# Feather-RTD.net
KiCad netlist of a schematic drawn in EAGLE
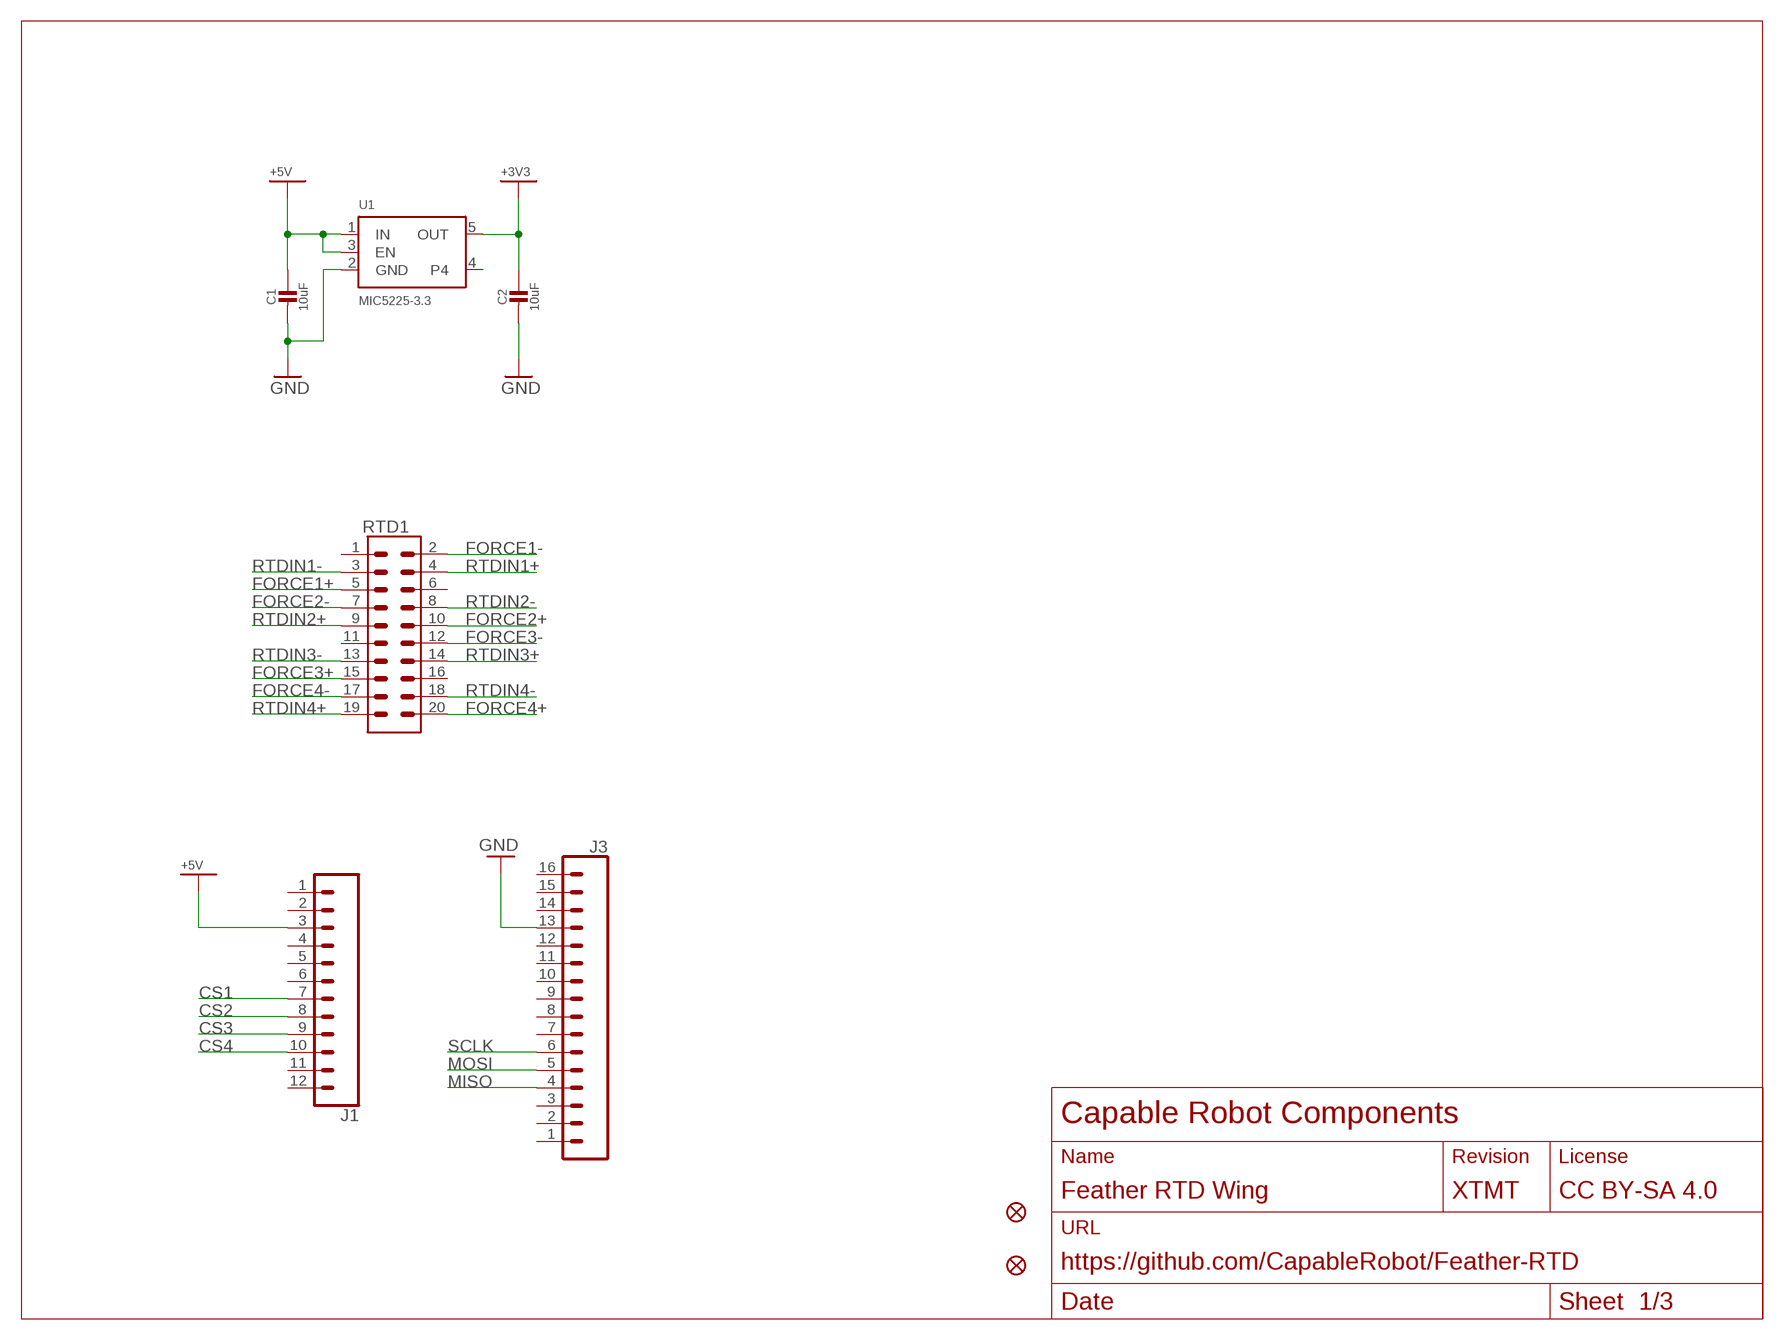
[diagram p0: schematic, sheet 1]
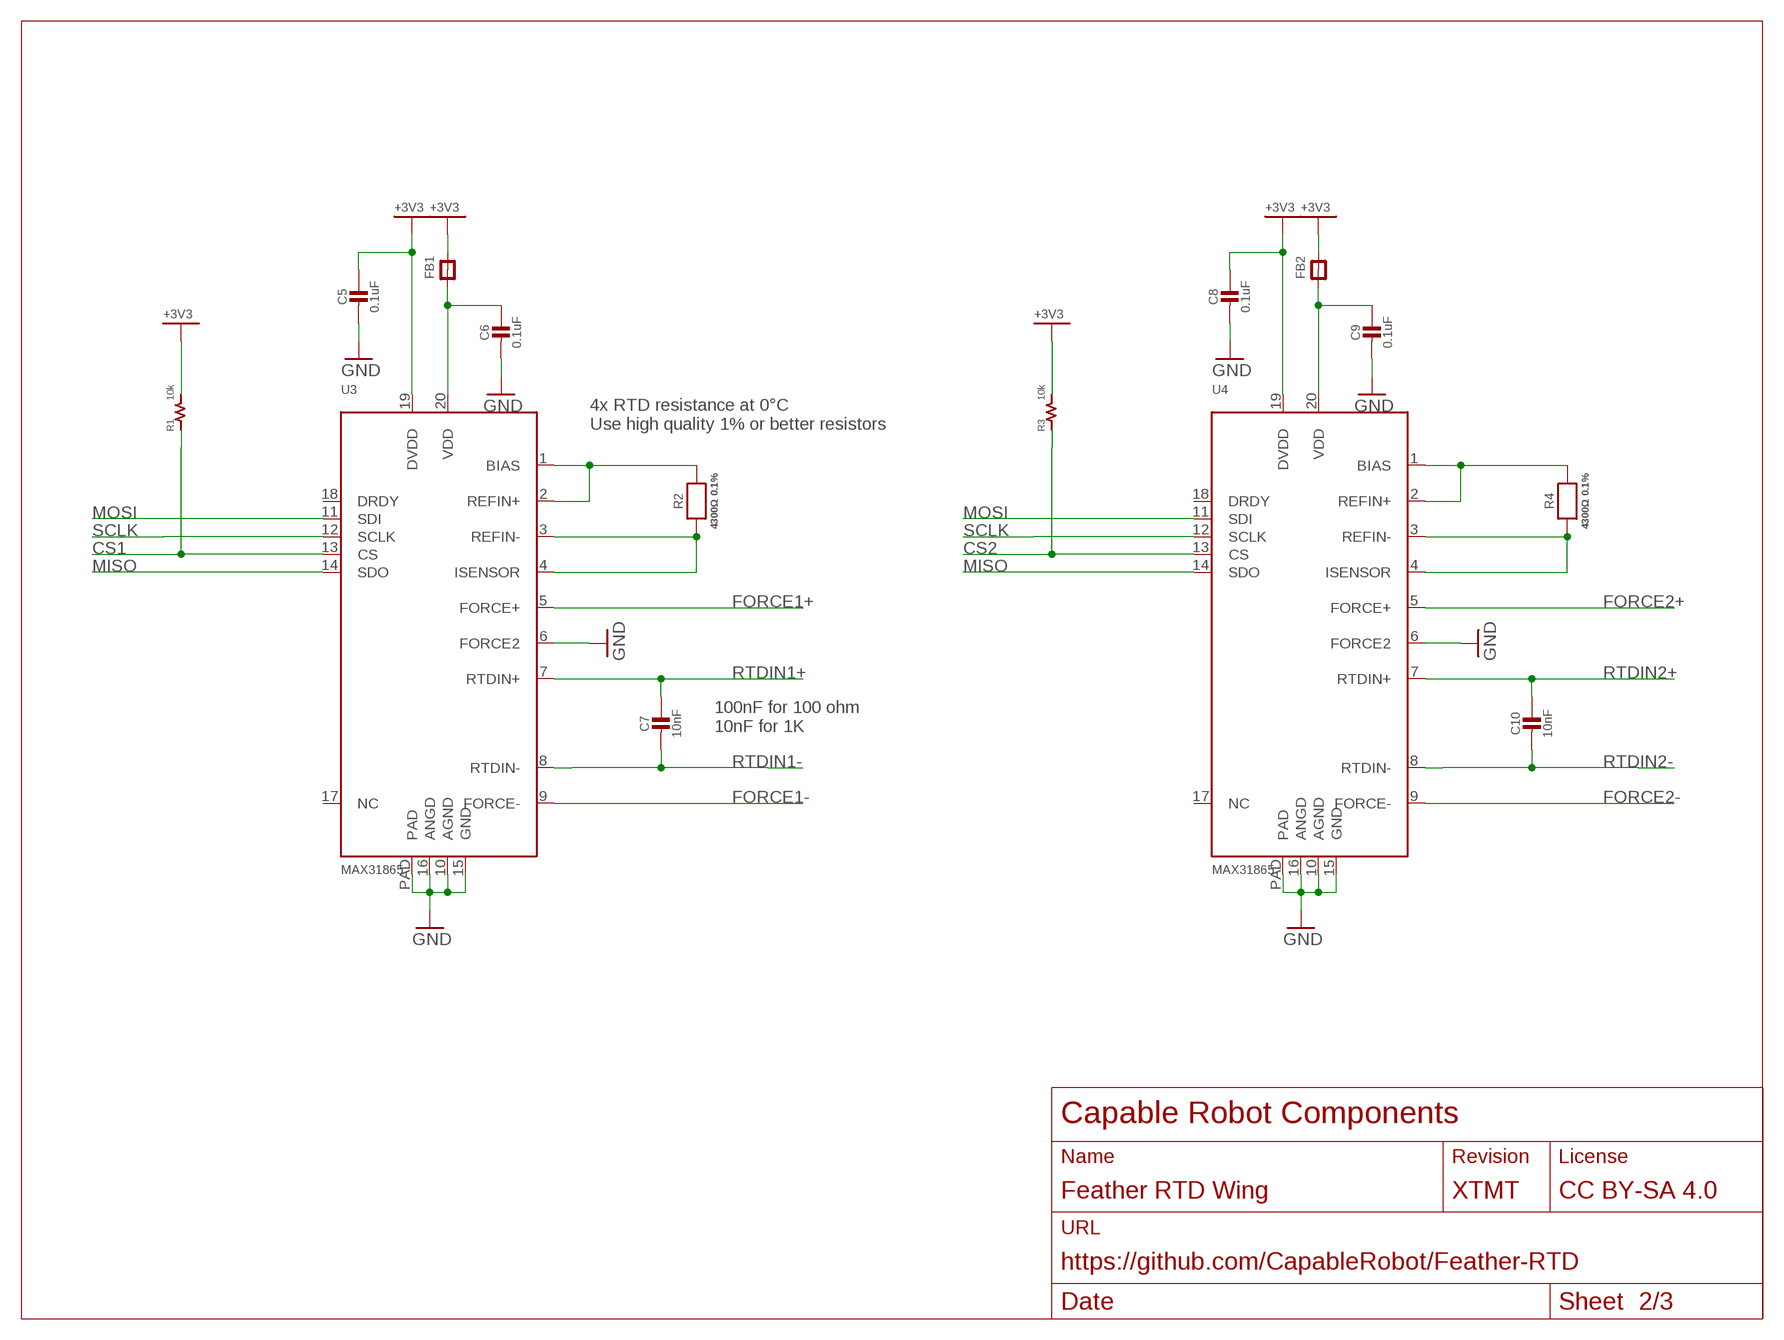
[diagram p1: schematic, sheet 2]
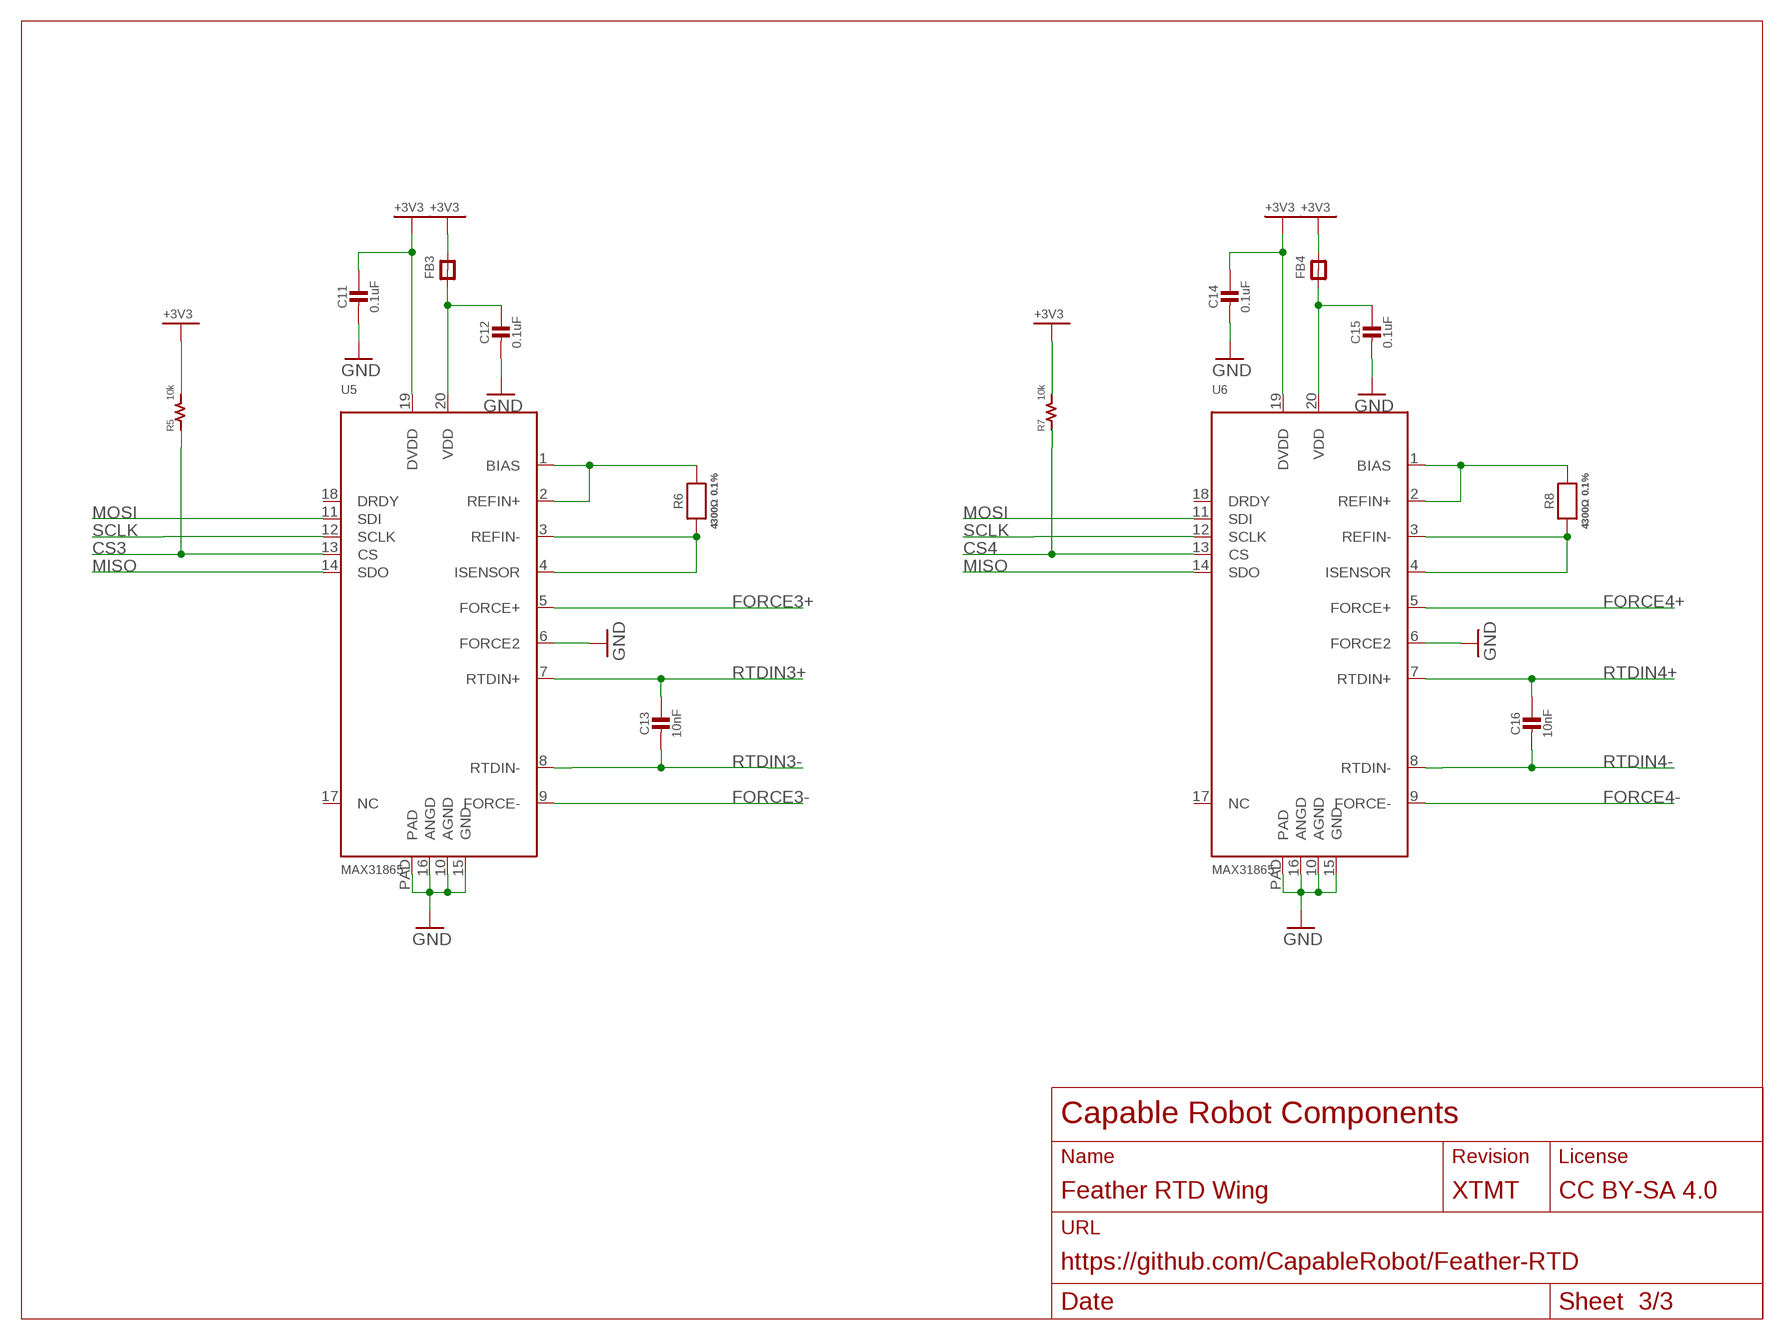
[diagram p2: schematic, sheet 3]

(export (version "E")
  (design (tool "Eeschema 10.0.6"))
  (components
    (comp (ref "C11")
      (value "0.1uF")
      (footprint "eagle-import:0805-NO")
      (libsource (lib "eagle-import") (part "CAP_CERAMIC0805-NOOUTLINE"))
    )
    (comp (ref "C12")
      (value "0.1uF")
      (footprint "eagle-import:0805-NO")
      (libsource (lib "eagle-import") (part "CAP_CERAMIC0805-NOOUTLINE"))
    )
    (comp (ref "C13")
      (value "10nF")
      (footprint "eagle-import:0805-NO")
      (libsource (lib "eagle-import") (part "CAP_CERAMIC0805-NOOUTLINE"))
    )
    (comp (ref "C14")
      (value "0.1uF")
      (footprint "eagle-import:0805-NO")
      (libsource (lib "eagle-import") (part "CAP_CERAMIC0805-NOOUTLINE"))
    )
    (comp (ref "C15")
      (value "0.1uF")
      (footprint "eagle-import:0805-NO")
      (libsource (lib "eagle-import") (part "CAP_CERAMIC0805-NOOUTLINE"))
    )
    (comp (ref "C16")
      (value "10nF")
      (footprint "eagle-import:0805-NO")
      (libsource (lib "eagle-import") (part "CAP_CERAMIC0805-NOOUTLINE"))
    )
    (comp (ref "FB3")
      (value "FERRITE-0805NO")
      (footprint "eagle-import:0805-NO")
      (libsource (lib "eagle-import") (part "FERRITE-0805NO"))
    )
    (comp (ref "FB4")
      (value "FERRITE-0805NO")
      (footprint "eagle-import:0805-NO")
      (libsource (lib "eagle-import") (part "FERRITE-0805NO"))
    )
    (comp (ref "R5")
      (value "10k")
      (footprint "eagle-import:0603")
      (libsource (lib "eagle-import") (part "RES0603"))
    )
    (comp (ref "R6")
      (value "4300Ω 0.1%")
      (footprint "eagle-import:0805-NO")
      (libsource (lib "eagle-import") (part "RESISTOR0805_NOOUTLINE"))
    )
    (comp (ref "R7")
      (value "10k")
      (footprint "eagle-import:0603")
      (libsource (lib "eagle-import") (part "RES0603"))
    )
    (comp (ref "R8")
      (value "4300Ω 0.1%")
      (footprint "eagle-import:0805-NO")
      (libsource (lib "eagle-import") (part "RESISTOR0805_NOOUTLINE"))
    )
    (comp (ref "U5")
      (value "MAX31865")
      (footprint "eagle-import:QFN20_4MM_0.65MM")
      (libsource (lib "eagle-import") (part "TEMP_MAX31865"))
    )
    (comp (ref "U6")
      (value "MAX31865")
      (footprint "eagle-import:QFN20_4MM_0.65MM")
      (libsource (lib "eagle-import") (part "TEMP_MAX31865"))
    )
    (comp (ref "C5")
      (value "0.1uF")
      (footprint "eagle-import:0805-NO")
      (libsource (lib "eagle-import") (part "CAP_CERAMIC0805-NOOUTLINE"))
    )
    (comp (ref "C6")
      (value "0.1uF")
      (footprint "eagle-import:0805-NO")
      (libsource (lib "eagle-import") (part "CAP_CERAMIC0805-NOOUTLINE"))
    )
    (comp (ref "C7")
      (value "10nF")
      (footprint "eagle-import:0805-NO")
      (libsource (lib "eagle-import") (part "CAP_CERAMIC0805-NOOUTLINE"))
    )
    (comp (ref "C8")
      (value "0.1uF")
      (footprint "eagle-import:0805-NO")
      (libsource (lib "eagle-import") (part "CAP_CERAMIC0805-NOOUTLINE"))
    )
    (comp (ref "C9")
      (value "0.1uF")
      (footprint "eagle-import:0805-NO")
      (libsource (lib "eagle-import") (part "CAP_CERAMIC0805-NOOUTLINE"))
    )
    (comp (ref "C10")
      (value "10nF")
      (footprint "eagle-import:0805-NO")
      (libsource (lib "eagle-import") (part "CAP_CERAMIC0805-NOOUTLINE"))
    )
    (comp (ref "FB1")
      (value "FERRITE-0805NO")
      (footprint "eagle-import:0805-NO")
      (libsource (lib "eagle-import") (part "FERRITE-0805NO"))
    )
    (comp (ref "FB2")
      (value "FERRITE-0805NO")
      (footprint "eagle-import:0805-NO")
      (libsource (lib "eagle-import") (part "FERRITE-0805NO"))
    )
    (comp (ref "R1")
      (value "10k")
      (footprint "eagle-import:0603")
      (libsource (lib "eagle-import") (part "RES0603"))
    )
    (comp (ref "R2")
      (value "4300Ω 0.1%")
      (footprint "eagle-import:0805-NO")
      (libsource (lib "eagle-import") (part "RESISTOR0805_NOOUTLINE"))
    )
    (comp (ref "R3")
      (value "10k")
      (footprint "eagle-import:0603")
      (libsource (lib "eagle-import") (part "RES0603"))
    )
    (comp (ref "R4")
      (value "4300Ω 0.1%")
      (footprint "eagle-import:0805-NO")
      (libsource (lib "eagle-import") (part "RESISTOR0805_NOOUTLINE"))
    )
    (comp (ref "U3")
      (value "MAX31865")
      (footprint "eagle-import:QFN20_4MM_0.65MM")
      (libsource (lib "eagle-import") (part "TEMP_MAX31865"))
    )
    (comp (ref "U4")
      (value "MAX31865")
      (footprint "eagle-import:QFN20_4MM_0.65MM")
      (libsource (lib "eagle-import") (part "TEMP_MAX31865"))
    )
    (comp (ref "C1")
      (value "10uF")
      (footprint "eagle-import:0805-NO")
      (libsource (lib "eagle-import") (part "CAP_CERAMIC0805-NOOUTLINE"))
    )
    (comp (ref "C2")
      (value "10uF")
      (footprint "eagle-import:0805-NO")
      (libsource (lib "eagle-import") (part "CAP_CERAMIC0805-NOOUTLINE"))
    )
    (comp (ref "FID1")
      (value "FIDUCIAL\"\"")
      (footprint "eagle-import:FIDUCIAL_1MM")
      (libsource (lib "eagle-import") (part "FIDUCIAL{dblquote}{dblquote}"))
    )
    (comp (ref "FID2")
      (value "FIDUCIAL\"\"")
      (footprint "eagle-import:FIDUCIAL_1MM")
      (libsource (lib "eagle-import") (part "FIDUCIAL{dblquote}{dblquote}"))
    )
    (comp (ref "J1")
      (value "CONN_12NO_SILK")
      (footprint "eagle-import:1X12_NO_SILK")
      (libsource (lib "eagle-import") (part "CONN_12NO_SILK"))
    )
    (comp (ref "J3")
      (value "CONN_161X16_NO_SILK")
      (footprint "eagle-import:1X16_NO_SILK")
      (libsource (lib "eagle-import") (part "CONN_161X16_NO_SILK"))
    )
    (comp (ref "RTD1")
      (value "CONN-20")
      (footprint "eagle-import:CONN-2X10-050-SMT-ZT")
      (libsource (lib "eagle-import") (part "CONN-20"))
    )
    (comp (ref "U1")
      (value "MIC5225-3.3")
      (footprint "eagle-import:SOT23-5")
      (libsource (lib "eagle-import") (part "VREG_SOT23-5"))
    )
  )
  (nets
    (net (code "1") (name "+3V3") (class "Default")
      (node (ref "C11") (pin "1") (pinfunction "1_1") (pintype "passive"))
      (node (ref "C14") (pin "1") (pinfunction "1_1") (pintype "passive"))
      (node (ref "C2") (pin "1") (pinfunction "1_1") (pintype "passive"))
      (node (ref "C5") (pin "1") (pinfunction "1_1") (pintype "passive"))
      (node (ref "C8") (pin "1") (pinfunction "1_1") (pintype "passive"))
      (node (ref "FB1") (pin "2") (pinfunction "P$2_2") (pintype "passive"))
      (node (ref "FB2") (pin "2") (pinfunction "P$2_2") (pintype "passive"))
      (node (ref "FB3") (pin "2") (pinfunction "P$2_2") (pintype "passive"))
      (node (ref "FB4") (pin "2") (pinfunction "P$2_2") (pintype "passive"))
      (node (ref "R1") (pin "2") (pinfunction "2_2") (pintype "passive"))
      (node (ref "R3") (pin "2") (pinfunction "2_2") (pintype "passive"))
      (node (ref "R5") (pin "2") (pinfunction "2_2") (pintype "passive"))
      (node (ref "R7") (pin "2") (pinfunction "2_2") (pintype "passive"))
      (node (ref "U1") (pin "5") (pinfunction "OUT_5") (pintype "power_in"))
      (node (ref "U3") (pin "19") (pinfunction "DVDD_19") (pintype "power_in"))
      (node (ref "U4") (pin "19") (pinfunction "DVDD_19") (pintype "power_in"))
      (node (ref "U5") (pin "19") (pinfunction "DVDD_19") (pintype "power_in"))
      (node (ref "U6") (pin "19") (pinfunction "DVDD_19") (pintype "power_in"))
    )
    (net (code "2") (name "+5V") (class "Default")
      (node (ref "C1") (pin "1") (pinfunction "1_1") (pintype "passive"))
      (node (ref "J1") (pin "3") (pinfunction "3_3") (pintype "passive"))
      (node (ref "U1") (pin "1") (pinfunction "IN_1") (pintype "power_in"))
      (node (ref "U1") (pin "3") (pinfunction "EN_3") (pintype "input"))
    )
    (net (code "3") (name "CS1") (class "Default")
      (node (ref "J1") (pin "7") (pinfunction "7_7") (pintype "passive"))
      (node (ref "R1") (pin "1") (pinfunction "1_1") (pintype "passive"))
      (node (ref "U3") (pin "13") (pinfunction "CS_13") (pintype "input"))
    )
    (net (code "4") (name "CS2") (class "Default")
      (node (ref "J1") (pin "8") (pinfunction "8_8") (pintype "passive"))
      (node (ref "R3") (pin "1") (pinfunction "1_1") (pintype "passive"))
      (node (ref "U4") (pin "13") (pinfunction "CS_13") (pintype "input"))
    )
    (net (code "5") (name "CS3") (class "Default")
      (node (ref "J1") (pin "9") (pinfunction "9_9") (pintype "passive"))
      (node (ref "R5") (pin "1") (pinfunction "1_1") (pintype "passive"))
      (node (ref "U5") (pin "13") (pinfunction "CS_13") (pintype "input"))
    )
    (net (code "6") (name "CS4") (class "Default")
      (node (ref "J1") (pin "10") (pinfunction "10_10") (pintype "passive"))
      (node (ref "R7") (pin "1") (pinfunction "1_1") (pintype "passive"))
      (node (ref "U6") (pin "13") (pinfunction "CS_13") (pintype "input"))
    )
    (net (code "7") (name "FORCE1+") (class "Default")
      (node (ref "RTD1") (pin "5") (pinfunction "P$5_5") (pintype "bidirectional"))
      (node (ref "U3") (pin "5") (pinfunction "FORCE+_5") (pintype "output"))
    )
    (net (code "8") (name "FORCE1-") (class "Default")
      (node (ref "RTD1") (pin "2") (pinfunction "P$2_2") (pintype "bidirectional"))
      (node (ref "U3") (pin "9") (pinfunction "FORCE-_9") (pintype "input"))
    )
    (net (code "9") (name "FORCE2+") (class "Default")
      (node (ref "RTD1") (pin "10") (pinfunction "P$10_10") (pintype "bidirectional"))
      (node (ref "U4") (pin "5") (pinfunction "FORCE+_5") (pintype "output"))
    )
    (net (code "10") (name "FORCE2-") (class "Default")
      (node (ref "RTD1") (pin "7") (pinfunction "P$7_7") (pintype "bidirectional"))
      (node (ref "U4") (pin "9") (pinfunction "FORCE-_9") (pintype "input"))
    )
    (net (code "11") (name "FORCE3+") (class "Default")
      (node (ref "RTD1") (pin "15") (pinfunction "P$15_15") (pintype "bidirectional"))
      (node (ref "U5") (pin "5") (pinfunction "FORCE+_5") (pintype "output"))
    )
    (net (code "12") (name "FORCE3-") (class "Default")
      (node (ref "RTD1") (pin "12") (pinfunction "P$12_12") (pintype "bidirectional"))
      (node (ref "U5") (pin "9") (pinfunction "FORCE-_9") (pintype "input"))
    )
    (net (code "13") (name "FORCE4+") (class "Default")
      (node (ref "RTD1") (pin "20") (pinfunction "P$20_20") (pintype "bidirectional"))
      (node (ref "U6") (pin "5") (pinfunction "FORCE+_5") (pintype "output"))
    )
    (net (code "14") (name "FORCE4-") (class "Default")
      (node (ref "RTD1") (pin "17") (pinfunction "P$17_17") (pintype "bidirectional"))
      (node (ref "U6") (pin "9") (pinfunction "FORCE-_9") (pintype "input"))
    )
    (net (code "15") (name "GND") (class "Default")
      (node (ref "C1") (pin "2") (pinfunction "2_2") (pintype "passive"))
      (node (ref "C11") (pin "2") (pinfunction "2_2") (pintype "passive"))
      (node (ref "C12") (pin "2") (pinfunction "2_2") (pintype "passive"))
      (node (ref "C14") (pin "2") (pinfunction "2_2") (pintype "passive"))
      (node (ref "C15") (pin "2") (pinfunction "2_2") (pintype "passive"))
      (node (ref "C2") (pin "2") (pinfunction "2_2") (pintype "passive"))
      (node (ref "C5") (pin "2") (pinfunction "2_2") (pintype "passive"))
      (node (ref "C6") (pin "2") (pinfunction "2_2") (pintype "passive"))
      (node (ref "C8") (pin "2") (pinfunction "2_2") (pintype "passive"))
      (node (ref "C9") (pin "2") (pinfunction "2_2") (pintype "passive"))
      (node (ref "J3") (pin "13") (pinfunction "13_13") (pintype "passive"))
      (node (ref "U1") (pin "2") (pinfunction "GND_2") (pintype "power_in"))
      (node (ref "U3") (pin "10") (pinfunction "AGND_10") (pintype "power_in"))
      (node (ref "U3") (pin "15") (pinfunction "GND_15") (pintype "power_in"))
      (node (ref "U3") (pin "16") (pinfunction "ANGD_16") (pintype "power_in"))
      (node (ref "U3") (pin "6") (pinfunction "FORCE2_6") (pintype "bidirectional"))
      (node (ref "U3") (pin "PAD") (pinfunction "PAD_PAD") (pintype "power_in"))
      (node (ref "U4") (pin "10") (pinfunction "AGND_10") (pintype "power_in"))
      (node (ref "U4") (pin "15") (pinfunction "GND_15") (pintype "power_in"))
      (node (ref "U4") (pin "16") (pinfunction "ANGD_16") (pintype "power_in"))
      (node (ref "U4") (pin "6") (pinfunction "FORCE2_6") (pintype "bidirectional"))
      (node (ref "U4") (pin "PAD") (pinfunction "PAD_PAD") (pintype "power_in"))
      (node (ref "U5") (pin "10") (pinfunction "AGND_10") (pintype "power_in"))
      (node (ref "U5") (pin "15") (pinfunction "GND_15") (pintype "power_in"))
      (node (ref "U5") (pin "16") (pinfunction "ANGD_16") (pintype "power_in"))
      (node (ref "U5") (pin "6") (pinfunction "FORCE2_6") (pintype "bidirectional"))
      (node (ref "U5") (pin "PAD") (pinfunction "PAD_PAD") (pintype "power_in"))
      (node (ref "U6") (pin "10") (pinfunction "AGND_10") (pintype "power_in"))
      (node (ref "U6") (pin "15") (pinfunction "GND_15") (pintype "power_in"))
      (node (ref "U6") (pin "16") (pinfunction "ANGD_16") (pintype "power_in"))
      (node (ref "U6") (pin "6") (pinfunction "FORCE2_6") (pintype "bidirectional"))
      (node (ref "U6") (pin "PAD") (pinfunction "PAD_PAD") (pintype "power_in"))
    )
    (net (code "16") (name "MISO") (class "Default")
      (node (ref "J3") (pin "4") (pinfunction "4_4") (pintype "passive"))
      (node (ref "U3") (pin "14") (pinfunction "SDO_14") (pintype "output"))
      (node (ref "U4") (pin "14") (pinfunction "SDO_14") (pintype "output"))
      (node (ref "U5") (pin "14") (pinfunction "SDO_14") (pintype "output"))
      (node (ref "U6") (pin "14") (pinfunction "SDO_14") (pintype "output"))
    )
    (net (code "17") (name "MOSI") (class "Default")
      (node (ref "J3") (pin "5") (pinfunction "5_5") (pintype "passive"))
      (node (ref "U3") (pin "11") (pinfunction "SDI_11") (pintype "input"))
      (node (ref "U4") (pin "11") (pinfunction "SDI_11") (pintype "input"))
      (node (ref "U5") (pin "11") (pinfunction "SDI_11") (pintype "input"))
      (node (ref "U6") (pin "11") (pinfunction "SDI_11") (pintype "input"))
    )
    (net (code "18") (name "Net-(FB1-P$1)") (class "Default")
      (node (ref "C6") (pin "1") (pinfunction "1_1") (pintype "passive"))
      (node (ref "FB1") (pin "1") (pinfunction "P$1_1") (pintype "passive"))
      (node (ref "U3") (pin "20") (pinfunction "VDD_20") (pintype "power_in"))
    )
    (net (code "19") (name "Net-(FB2-P$1)") (class "Default")
      (node (ref "C9") (pin "1") (pinfunction "1_1") (pintype "passive"))
      (node (ref "FB2") (pin "1") (pinfunction "P$1_1") (pintype "passive"))
      (node (ref "U4") (pin "20") (pinfunction "VDD_20") (pintype "power_in"))
    )
    (net (code "20") (name "Net-(FB3-P$1)") (class "Default")
      (node (ref "C12") (pin "1") (pinfunction "1_1") (pintype "passive"))
      (node (ref "FB3") (pin "1") (pinfunction "P$1_1") (pintype "passive"))
      (node (ref "U5") (pin "20") (pinfunction "VDD_20") (pintype "power_in"))
    )
    (net (code "21") (name "Net-(FB4-P$1)") (class "Default")
      (node (ref "C15") (pin "1") (pinfunction "1_1") (pintype "passive"))
      (node (ref "FB4") (pin "1") (pinfunction "P$1_1") (pintype "passive"))
      (node (ref "U6") (pin "20") (pinfunction "VDD_20") (pintype "power_in"))
    )
    (net (code "22") (name "Net-(U3-BIAS)") (class "Default")
      (node (ref "R2") (pin "2") (pinfunction "2_2") (pintype "passive"))
      (node (ref "U3") (pin "1") (pinfunction "BIAS_1") (pintype "output"))
      (node (ref "U3") (pin "2") (pinfunction "REFIN+_2") (pintype "bidirectional"))
    )
    (net (code "23") (name "Net-(U3-ISENSOR)") (class "Default")
      (node (ref "R2") (pin "1") (pinfunction "1_1") (pintype "passive"))
      (node (ref "U3") (pin "3") (pinfunction "REFIN-_3") (pintype "bidirectional"))
      (node (ref "U3") (pin "4") (pinfunction "ISENSOR_4") (pintype "input"))
    )
    (net (code "24") (name "Net-(U4-BIAS)") (class "Default")
      (node (ref "R4") (pin "2") (pinfunction "2_2") (pintype "passive"))
      (node (ref "U4") (pin "1") (pinfunction "BIAS_1") (pintype "output"))
      (node (ref "U4") (pin "2") (pinfunction "REFIN+_2") (pintype "bidirectional"))
    )
    (net (code "25") (name "Net-(U4-ISENSOR)") (class "Default")
      (node (ref "R4") (pin "1") (pinfunction "1_1") (pintype "passive"))
      (node (ref "U4") (pin "3") (pinfunction "REFIN-_3") (pintype "bidirectional"))
      (node (ref "U4") (pin "4") (pinfunction "ISENSOR_4") (pintype "input"))
    )
    (net (code "26") (name "Net-(U5-BIAS)") (class "Default")
      (node (ref "R6") (pin "2") (pinfunction "2_2") (pintype "passive"))
      (node (ref "U5") (pin "1") (pinfunction "BIAS_1") (pintype "output"))
      (node (ref "U5") (pin "2") (pinfunction "REFIN+_2") (pintype "bidirectional"))
    )
    (net (code "27") (name "Net-(U5-ISENSOR)") (class "Default")
      (node (ref "R6") (pin "1") (pinfunction "1_1") (pintype "passive"))
      (node (ref "U5") (pin "3") (pinfunction "REFIN-_3") (pintype "bidirectional"))
      (node (ref "U5") (pin "4") (pinfunction "ISENSOR_4") (pintype "input"))
    )
    (net (code "28") (name "Net-(U6-BIAS)") (class "Default")
      (node (ref "R8") (pin "2") (pinfunction "2_2") (pintype "passive"))
      (node (ref "U6") (pin "1") (pinfunction "BIAS_1") (pintype "output"))
      (node (ref "U6") (pin "2") (pinfunction "REFIN+_2") (pintype "bidirectional"))
    )
    (net (code "29") (name "Net-(U6-ISENSOR)") (class "Default")
      (node (ref "R8") (pin "1") (pinfunction "1_1") (pintype "passive"))
      (node (ref "U6") (pin "3") (pinfunction "REFIN-_3") (pintype "bidirectional"))
      (node (ref "U6") (pin "4") (pinfunction "ISENSOR_4") (pintype "input"))
    )
    (net (code "30") (name "RTDIN1+") (class "Default")
      (node (ref "C7") (pin "1") (pinfunction "1_1") (pintype "passive"))
      (node (ref "RTD1") (pin "4") (pinfunction "P$4_4") (pintype "bidirectional"))
      (node (ref "U3") (pin "7") (pinfunction "RTDIN+_7") (pintype "bidirectional"))
    )
    (net (code "31") (name "RTDIN1-") (class "Default")
      (node (ref "C7") (pin "2") (pinfunction "2_2") (pintype "passive"))
      (node (ref "RTD1") (pin "3") (pinfunction "P$3_3") (pintype "bidirectional"))
      (node (ref "U3") (pin "8") (pinfunction "RTDIN-_8") (pintype "bidirectional"))
    )
    (net (code "32") (name "RTDIN2+") (class "Default")
      (node (ref "C10") (pin "1") (pinfunction "1_1") (pintype "passive"))
      (node (ref "RTD1") (pin "9") (pinfunction "P$9_9") (pintype "bidirectional"))
      (node (ref "U4") (pin "7") (pinfunction "RTDIN+_7") (pintype "bidirectional"))
    )
    (net (code "33") (name "RTDIN2-") (class "Default")
      (node (ref "C10") (pin "2") (pinfunction "2_2") (pintype "passive"))
      (node (ref "RTD1") (pin "8") (pinfunction "P$8_8") (pintype "bidirectional"))
      (node (ref "U4") (pin "8") (pinfunction "RTDIN-_8") (pintype "bidirectional"))
    )
    (net (code "34") (name "RTDIN3+") (class "Default")
      (node (ref "C13") (pin "1") (pinfunction "1_1") (pintype "passive"))
      (node (ref "RTD1") (pin "14") (pinfunction "P$14_14") (pintype "bidirectional"))
      (node (ref "U5") (pin "7") (pinfunction "RTDIN+_7") (pintype "bidirectional"))
    )
    (net (code "35") (name "RTDIN3-") (class "Default")
      (node (ref "C13") (pin "2") (pinfunction "2_2") (pintype "passive"))
      (node (ref "RTD1") (pin "13") (pinfunction "P$13_13") (pintype "bidirectional"))
      (node (ref "U5") (pin "8") (pinfunction "RTDIN-_8") (pintype "bidirectional"))
    )
    (net (code "36") (name "RTDIN4+") (class "Default")
      (node (ref "C16") (pin "1") (pinfunction "1_1") (pintype "passive"))
      (node (ref "RTD1") (pin "19") (pinfunction "P$19_19") (pintype "bidirectional"))
      (node (ref "U6") (pin "7") (pinfunction "RTDIN+_7") (pintype "bidirectional"))
    )
    (net (code "37") (name "RTDIN4-") (class "Default")
      (node (ref "C16") (pin "2") (pinfunction "2_2") (pintype "passive"))
      (node (ref "RTD1") (pin "18") (pinfunction "P$18_18") (pintype "bidirectional"))
      (node (ref "U6") (pin "8") (pinfunction "RTDIN-_8") (pintype "bidirectional"))
    )
    (net (code "38") (name "SCLK") (class "Default")
      (node (ref "J3") (pin "6") (pinfunction "6_6") (pintype "passive"))
      (node (ref "U3") (pin "12") (pinfunction "SCLK_12") (pintype "input"))
      (node (ref "U4") (pin "12") (pinfunction "SCLK_12") (pintype "input"))
      (node (ref "U5") (pin "12") (pinfunction "SCLK_12") (pintype "input"))
      (node (ref "U6") (pin "12") (pinfunction "SCLK_12") (pintype "input"))
    )
    (net (code "39") (name "unconnected-(J1-Pad1)") (class "Default")
      (node (ref "J1") (pin "1") (pinfunction "1_1") (pintype "passive"))
    )
    (net (code "40") (name "unconnected-(J1-Pad2)") (class "Default")
      (node (ref "J1") (pin "2") (pinfunction "2_2") (pintype "passive"))
    )
    (net (code "41") (name "unconnected-(J1-Pad4)") (class "Default")
      (node (ref "J1") (pin "4") (pinfunction "4_4") (pintype "passive"))
    )
    (net (code "42") (name "unconnected-(J1-Pad5)") (class "Default")
      (node (ref "J1") (pin "5") (pinfunction "5_5") (pintype "passive"))
    )
    (net (code "43") (name "unconnected-(J1-Pad6)") (class "Default")
      (node (ref "J1") (pin "6") (pinfunction "6_6") (pintype "passive"))
    )
    (net (code "44") (name "unconnected-(J1-Pad11)") (class "Default")
      (node (ref "J1") (pin "11") (pinfunction "11_11") (pintype "passive"))
    )
    (net (code "45") (name "unconnected-(J1-Pad12)") (class "Default")
      (node (ref "J1") (pin "12") (pinfunction "12_12") (pintype "passive"))
    )
    (net (code "46") (name "unconnected-(J3-Pad1)") (class "Default")
      (node (ref "J3") (pin "1") (pinfunction "1_1") (pintype "passive"))
    )
    (net (code "47") (name "unconnected-(J3-Pad2)") (class "Default")
      (node (ref "J3") (pin "2") (pinfunction "2_2") (pintype "passive"))
    )
    (net (code "48") (name "unconnected-(J3-Pad3)") (class "Default")
      (node (ref "J3") (pin "3") (pinfunction "3_3") (pintype "passive"))
    )
    (net (code "49") (name "unconnected-(J3-Pad7)") (class "Default")
      (node (ref "J3") (pin "7") (pinfunction "7_7") (pintype "passive"))
    )
    (net (code "50") (name "unconnected-(J3-Pad8)") (class "Default")
      (node (ref "J3") (pin "8") (pinfunction "8_8") (pintype "passive"))
    )
    (net (code "51") (name "unconnected-(J3-Pad9)") (class "Default")
      (node (ref "J3") (pin "9") (pinfunction "9_9") (pintype "passive"))
    )
    (net (code "52") (name "unconnected-(J3-Pad10)") (class "Default")
      (node (ref "J3") (pin "10") (pinfunction "10_10") (pintype "passive"))
    )
    (net (code "53") (name "unconnected-(J3-Pad11)") (class "Default")
      (node (ref "J3") (pin "11") (pinfunction "11_11") (pintype "passive"))
    )
    (net (code "54") (name "unconnected-(J3-Pad12)") (class "Default")
      (node (ref "J3") (pin "12") (pinfunction "12_12") (pintype "passive"))
    )
    (net (code "55") (name "unconnected-(J3-Pad14)") (class "Default")
      (node (ref "J3") (pin "14") (pinfunction "14_14") (pintype "passive"))
    )
    (net (code "56") (name "unconnected-(J3-Pad15)") (class "Default")
      (node (ref "J3") (pin "15") (pinfunction "15_15") (pintype "passive"))
    )
    (net (code "57") (name "unconnected-(J3-Pad16)") (class "Default")
      (node (ref "J3") (pin "16") (pinfunction "16_16") (pintype "passive"))
    )
    (net (code "58") (name "unconnected-(RTD1-P$1-Pad1)") (class "Default")
      (node (ref "RTD1") (pin "1") (pinfunction "P$1_1") (pintype "bidirectional"))
    )
    (net (code "59") (name "unconnected-(RTD1-P$6-Pad6)") (class "Default")
      (node (ref "RTD1") (pin "6") (pinfunction "P$6_6") (pintype "bidirectional"))
    )
    (net (code "60") (name "unconnected-(RTD1-P$11-Pad11)") (class "Default")
      (node (ref "RTD1") (pin "11") (pinfunction "P$11_11") (pintype "bidirectional"))
    )
    (net (code "61") (name "unconnected-(RTD1-P$16-Pad16)") (class "Default")
      (node (ref "RTD1") (pin "16") (pinfunction "P$16_16") (pintype "bidirectional"))
    )
    (net (code "62") (name "unconnected-(U1-P4-Pad4)") (class "Default")
      (node (ref "U1") (pin "4") (pinfunction "P4_4") (pintype "bidirectional"))
    )
    (net (code "63") (name "unconnected-(U3-DRDY-Pad18)") (class "Default")
      (node (ref "U3") (pin "18") (pinfunction "DRDY_18") (pintype "output"))
    )
    (net (code "64") (name "unconnected-(U3-NC-Pad17)") (class "Default")
      (node (ref "U3") (pin "17") (pinfunction "NC_17") (pintype "no_connect"))
    )
    (net (code "65") (name "unconnected-(U4-DRDY-Pad18)") (class "Default")
      (node (ref "U4") (pin "18") (pinfunction "DRDY_18") (pintype "output"))
    )
    (net (code "66") (name "unconnected-(U4-NC-Pad17)") (class "Default")
      (node (ref "U4") (pin "17") (pinfunction "NC_17") (pintype "no_connect"))
    )
    (net (code "67") (name "unconnected-(U5-DRDY-Pad18)") (class "Default")
      (node (ref "U5") (pin "18") (pinfunction "DRDY_18") (pintype "output"))
    )
    (net (code "68") (name "unconnected-(U5-NC-Pad17)") (class "Default")
      (node (ref "U5") (pin "17") (pinfunction "NC_17") (pintype "no_connect"))
    )
    (net (code "69") (name "unconnected-(U6-DRDY-Pad18)") (class "Default")
      (node (ref "U6") (pin "18") (pinfunction "DRDY_18") (pintype "output"))
    )
    (net (code "70") (name "unconnected-(U6-NC-Pad17)") (class "Default")
      (node (ref "U6") (pin "17") (pinfunction "NC_17") (pintype "no_connect"))
    )
  )
)
